# Carte-Marteaux.net
KiCad netlist of a schematic drawn in EAGLE
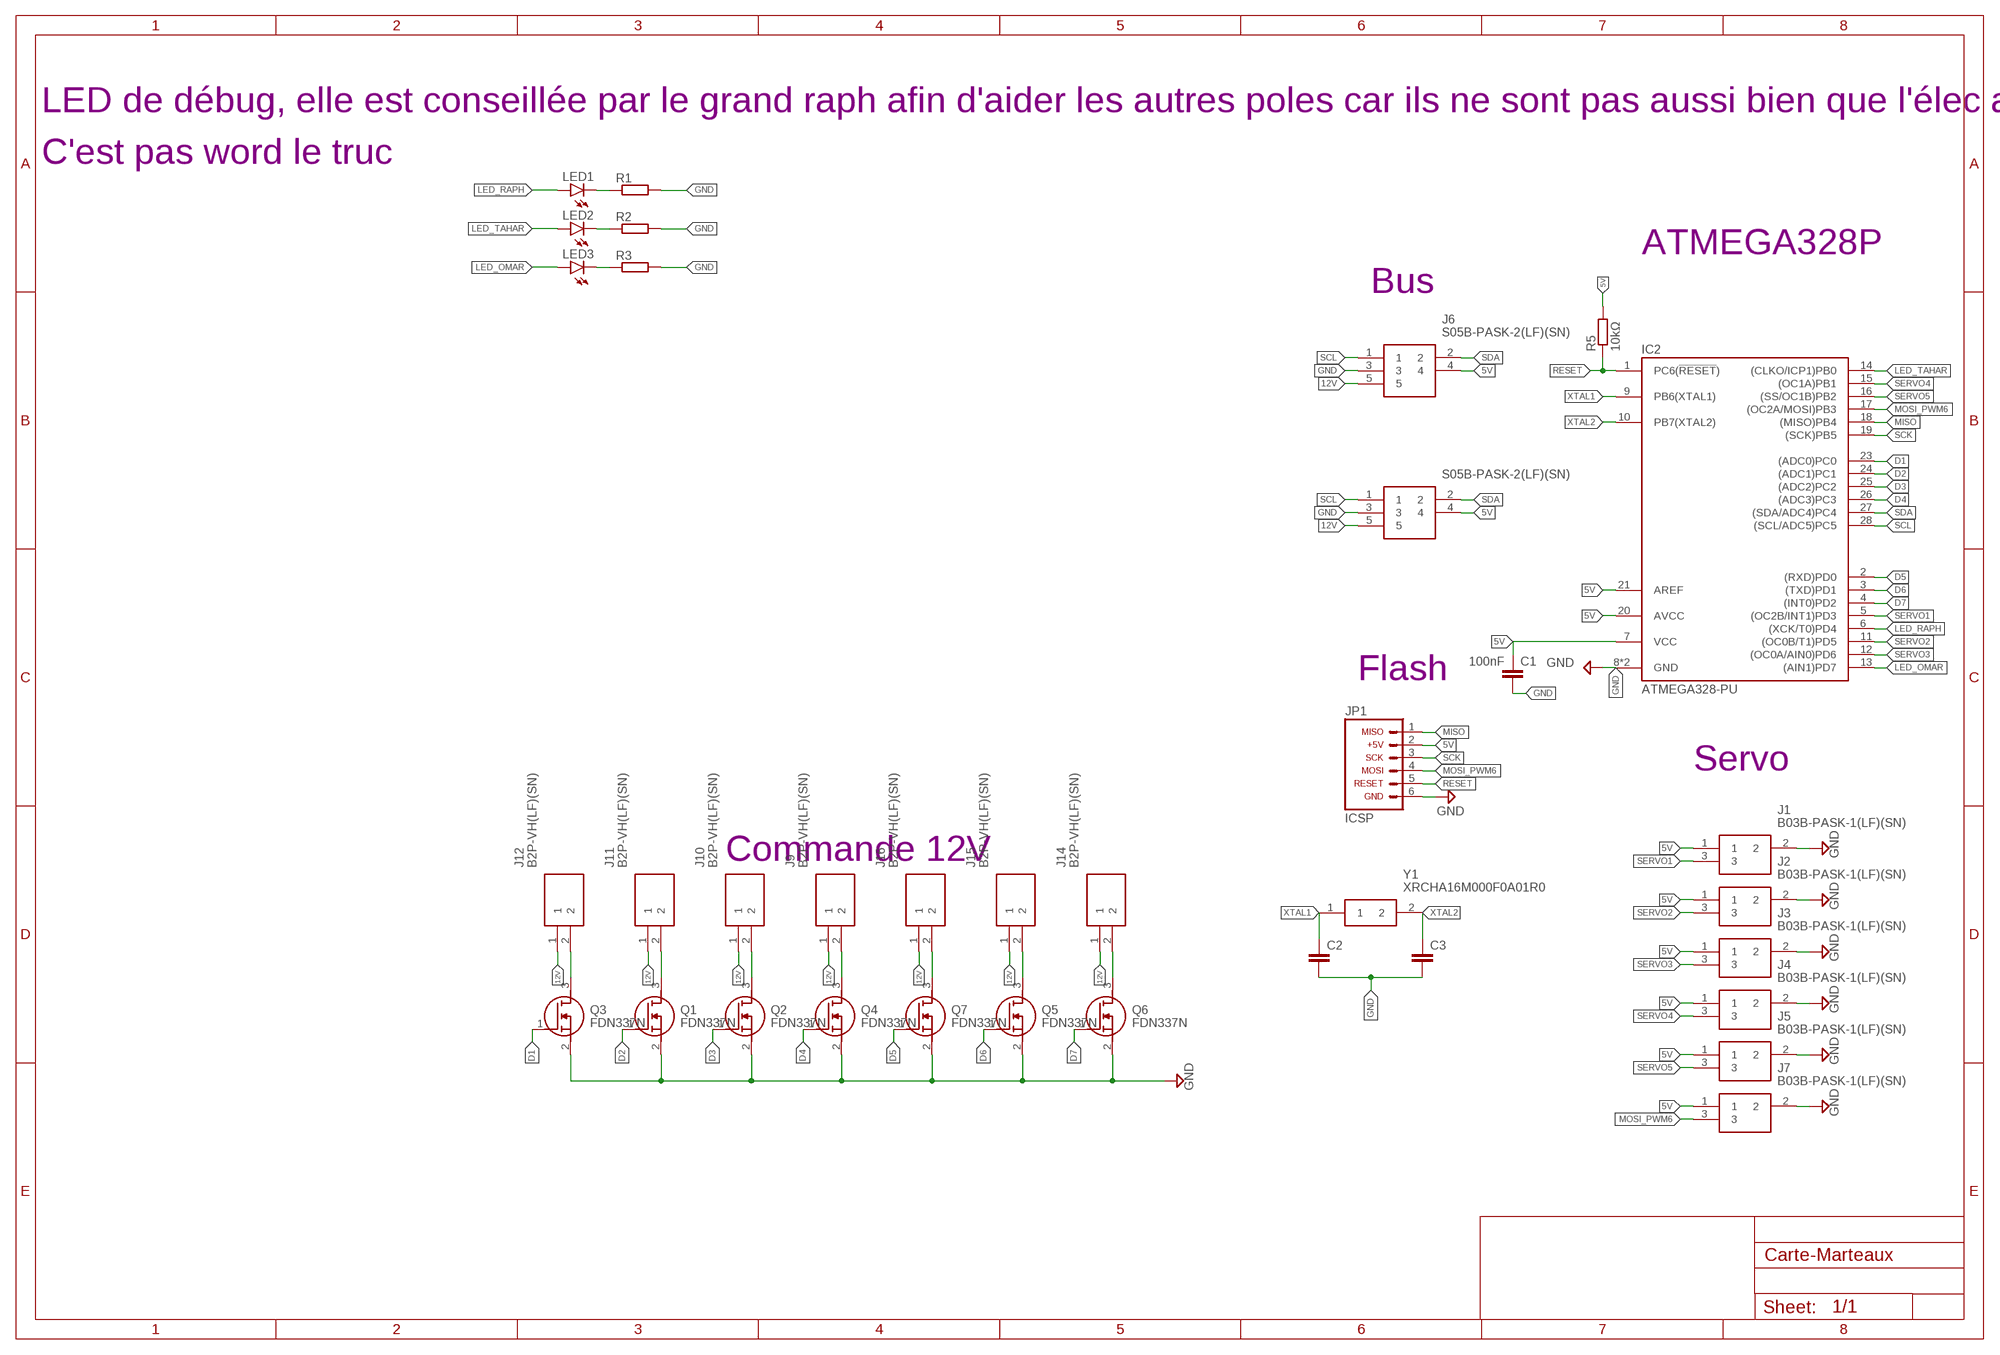
[diagram p0: schematic, sheet 1]

(export (version "E")
  (design (tool "Eeschema 10.0.6"))
  (components
    (comp (ref "C1")
      (value "100nF")
      (footprint "eagle-import:C0805")
      (libsource (lib "eagle-import") (part "C-EUC0805"))
    )
    (comp (ref "C2")
      (value "C-EUC0402")
      (footprint "eagle-import:C0402")
      (libsource (lib "eagle-import") (part "C-EUC0402"))
    )
    (comp (ref "C3")
      (value "C-EUC0402")
      (footprint "eagle-import:C0402")
      (libsource (lib "eagle-import") (part "C-EUC0402"))
    )
    (comp (ref "IC2")
      (value "ATMEGA328-PU")
      (footprint "eagle-import:DIL28")
      (fields (field (name "MF") "Microchip Technology"))
      (libsource (lib "eagle-import") (part "ATMEGA328-PU"))
    )
    (comp (ref "J1")
      (value "B03B-PASK-1(LF)(SN)")
      (footprint "eagle-import:B03BPASK1LFSN")
      (libsource (lib "eagle-import") (part "B03B-PASK-1(LF)(SN)"))
    )
    (comp (ref "J2")
      (value "B03B-PASK-1(LF)(SN)")
      (footprint "eagle-import:B03BPASK1LFSN")
      (libsource (lib "eagle-import") (part "B03B-PASK-1(LF)(SN)"))
    )
    (comp (ref "J3")
      (value "B03B-PASK-1(LF)(SN)")
      (footprint "eagle-import:B03BPASK1LFSN")
      (libsource (lib "eagle-import") (part "B03B-PASK-1(LF)(SN)"))
    )
    (comp (ref "J4")
      (value "B03B-PASK-1(LF)(SN)")
      (footprint "eagle-import:B03BPASK1LFSN")
      (libsource (lib "eagle-import") (part "B03B-PASK-1(LF)(SN)"))
    )
    (comp (ref "J5")
      (value "B03B-PASK-1(LF)(SN)")
      (footprint "eagle-import:B03BPASK1LFSN")
      (libsource (lib "eagle-import") (part "B03B-PASK-1(LF)(SN)"))
    )
    (comp (ref "J6")
      (value "S05B-PASK-2(LF)(SN)")
      (footprint "eagle-import:S05B-PASK-2(LF)(SN)")
      (libsource (lib "eagle-import") (part "S05B-PASK-2(LF)(SN)"))
    )
    (comp (ref "J7")
      (value "B03B-PASK-1(LF)(SN)")
      (footprint "eagle-import:B03BPASK1LFSN")
      (libsource (lib "eagle-import") (part "B03B-PASK-1(LF)(SN)"))
    )
    (comp (ref "J8")
      (value "S05B-PASK-2(LF)(SN)")
      (footprint "eagle-import:S05B-PASK-2(LF)(SN)")
      (libsource (lib "eagle-import") (part "S05B-PASK-2(LF)(SN)"))
    )
    (comp (ref "J9")
      (value "B2P-VH(LF)(SN)")
      (footprint "eagle-import:SHDR2W114P0X396_1X2_786X850X94")
      (fields (field (name "RS_PART_NUMBER") "8201147P"))
      (libsource (lib "eagle-import") (part "B2P-VH(LF)(SN)"))
    )
    (comp (ref "J10")
      (value "B2P-VH(LF)(SN)")
      (footprint "eagle-import:SHDR2W114P0X396_1X2_786X850X94")
      (fields (field (name "RS_PART_NUMBER") "8201147P"))
      (libsource (lib "eagle-import") (part "B2P-VH(LF)(SN)"))
    )
    (comp (ref "J11")
      (value "B2P-VH(LF)(SN)")
      (footprint "eagle-import:SHDR2W114P0X396_1X2_786X850X94")
      (fields (field (name "RS_PART_NUMBER") "8201147P"))
      (libsource (lib "eagle-import") (part "B2P-VH(LF)(SN)"))
    )
    (comp (ref "J12")
      (value "B2P-VH(LF)(SN)")
      (footprint "eagle-import:SHDR2W114P0X396_1X2_786X850X94")
      (fields (field (name "RS_PART_NUMBER") "8201147P"))
      (libsource (lib "eagle-import") (part "B2P-VH(LF)(SN)"))
    )
    (comp (ref "J14")
      (value "B2P-VH(LF)(SN)")
      (footprint "eagle-import:SHDR2W114P0X396_1X2_786X850X94")
      (fields (field (name "RS_PART_NUMBER") "8201147P"))
      (libsource (lib "eagle-import") (part "B2P-VH(LF)(SN)"))
    )
    (comp (ref "J15")
      (value "B2P-VH(LF)(SN)")
      (footprint "eagle-import:SHDR2W114P0X396_1X2_786X850X94")
      (fields (field (name "RS_PART_NUMBER") "8201147P"))
      (libsource (lib "eagle-import") (part "B2P-VH(LF)(SN)"))
    )
    (comp (ref "J16")
      (value "B2P-VH(LF)(SN)")
      (footprint "eagle-import:SHDR2W114P0X396_1X2_786X850X94")
      (fields (field (name "RS_PART_NUMBER") "8201147P"))
      (libsource (lib "eagle-import") (part "B2P-VH(LF)(SN)"))
    )
    (comp (ref "JP1")
      (value "ARDUINO_CONN-ICSP")
      (footprint "eagle-import:CONN-2X03")
      (libsource (lib "eagle-import") (part "ARDUINO_CONN-ICSP"))
    )
    (comp (ref "LED1")
      (value "LEDCHIP-LED0805")
      (footprint "eagle-import:CHIP-LED0805")
      (libsource (lib "eagle-import") (part "LEDCHIP-LED0805"))
    )
    (comp (ref "LED2")
      (value "LEDCHIP-LED0805")
      (footprint "eagle-import:CHIP-LED0805")
      (libsource (lib "eagle-import") (part "LEDCHIP-LED0805"))
    )
    (comp (ref "LED3")
      (value "LEDCHIP-LED0805")
      (footprint "eagle-import:CHIP-LED0805")
      (libsource (lib "eagle-import") (part "LEDCHIP-LED0805"))
    )
    (comp (ref "Q1")
      (value "FDN337N")
      (footprint "eagle-import:SOT95P237X112-3N")
      (fields (field (name "MOUSER_PART_NUMBER") "512-FDN337N") (field (name "RS_PART_NUMBER") "6710429P"))
      (libsource (lib "eagle-import") (part "FDN337N"))
    )
    (comp (ref "Q2")
      (value "FDN337N")
      (footprint "eagle-import:SOT95P237X112-3N")
      (fields (field (name "MOUSER_PART_NUMBER") "512-FDN337N") (field (name "RS_PART_NUMBER") "6710429P"))
      (libsource (lib "eagle-import") (part "FDN337N"))
    )
    (comp (ref "Q3")
      (value "FDN337N")
      (footprint "eagle-import:SOT95P237X112-3N")
      (fields (field (name "MOUSER_PART_NUMBER") "512-FDN337N") (field (name "RS_PART_NUMBER") "6710429P"))
      (libsource (lib "eagle-import") (part "FDN337N"))
    )
    (comp (ref "Q4")
      (value "FDN337N")
      (footprint "eagle-import:SOT95P237X112-3N")
      (fields (field (name "MOUSER_PART_NUMBER") "512-FDN337N") (field (name "RS_PART_NUMBER") "6710429P"))
      (libsource (lib "eagle-import") (part "FDN337N"))
    )
    (comp (ref "Q5")
      (value "FDN337N")
      (footprint "eagle-import:SOT95P237X112-3N")
      (fields (field (name "MOUSER_PART_NUMBER") "512-FDN337N") (field (name "RS_PART_NUMBER") "6710429P"))
      (libsource (lib "eagle-import") (part "FDN337N"))
    )
    (comp (ref "Q6")
      (value "FDN337N")
      (footprint "eagle-import:SOT95P237X112-3N")
      (fields (field (name "MOUSER_PART_NUMBER") "512-FDN337N") (field (name "RS_PART_NUMBER") "6710429P"))
      (libsource (lib "eagle-import") (part "FDN337N"))
    )
    (comp (ref "Q7")
      (value "FDN337N")
      (footprint "eagle-import:SOT95P237X112-3N")
      (fields (field (name "MOUSER_PART_NUMBER") "512-FDN337N") (field (name "RS_PART_NUMBER") "6710429P"))
      (libsource (lib "eagle-import") (part "FDN337N"))
    )
    (comp (ref "R1")
      (value "R-EU_R0805")
      (footprint "eagle-import:R0805")
      (libsource (lib "eagle-import") (part "R-EU_R0805"))
    )
    (comp (ref "R2")
      (value "R-EU_R0805")
      (footprint "eagle-import:R0805")
      (libsource (lib "eagle-import") (part "R-EU_R0805"))
    )
    (comp (ref "R3")
      (value "R-EU_R0805")
      (footprint "eagle-import:R0805")
      (libsource (lib "eagle-import") (part "R-EU_R0805"))
    )
    (comp (ref "R5")
      (value "10kΩ")
      (footprint "eagle-import:R0805")
      (libsource (lib "eagle-import") (part "R-EU_R0805"))
    )
    (comp (ref "Y1")
      (value "XRCHA16M000F0A01R0")
      (footprint "eagle-import:XRCHA")
      (fields
        (field (name "MOUSER_PART_NUMBER") "81-XRCHA16M000F0A1R0")
        (field (name "RS_PART_NUMBER") "1446622")
      )
      (libsource (lib "eagle-import") (part "XRCHA16M000F0A01R0"))
    )
  )
  (nets
    (net (code "1") (name "5V") (class "Default")
      (node (ref "C1") (pin "1") (pinfunction "1_1") (pintype "passive"))
      (node (ref "IC2") (pin "20") (pinfunction "AVCC_20") (pintype "power_in"))
      (node (ref "IC2") (pin "21") (pinfunction "AREF_21") (pintype "passive"))
      (node (ref "IC2") (pin "7") (pinfunction "VCC_7") (pintype "power_in"))
      (node (ref "J1") (pin "1") (pinfunction "1_1") (pintype "bidirectional"))
      (node (ref "J2") (pin "1") (pinfunction "1_1") (pintype "bidirectional"))
      (node (ref "J3") (pin "1") (pinfunction "1_1") (pintype "bidirectional"))
      (node (ref "J4") (pin "1") (pinfunction "1_1") (pintype "bidirectional"))
      (node (ref "J5") (pin "1") (pinfunction "1_1") (pintype "bidirectional"))
      (node (ref "J6") (pin "4") (pinfunction "4_4") (pintype "bidirectional"))
      (node (ref "J7") (pin "1") (pinfunction "1_1") (pintype "bidirectional"))
      (node (ref "J8") (pin "4") (pinfunction "4_4") (pintype "bidirectional"))
      (node (ref "JP1") (pin "2") (pinfunction "2_2") (pintype "passive"))
      (node (ref "R5") (pin "2") (pinfunction "2_2") (pintype "passive"))
    )
    (net (code "2") (name "12V") (class "Default")
      (node (ref "J10") (pin "1") (pinfunction "1_1") (pintype "bidirectional"))
      (node (ref "J11") (pin "1") (pinfunction "1_1") (pintype "bidirectional"))
      (node (ref "J12") (pin "1") (pinfunction "1_1") (pintype "bidirectional"))
      (node (ref "J14") (pin "1") (pinfunction "1_1") (pintype "bidirectional"))
      (node (ref "J15") (pin "1") (pinfunction "1_1") (pintype "bidirectional"))
      (node (ref "J16") (pin "1") (pinfunction "1_1") (pintype "bidirectional"))
      (node (ref "J6") (pin "5") (pinfunction "5_5") (pintype "bidirectional"))
      (node (ref "J8") (pin "5") (pinfunction "5_5") (pintype "bidirectional"))
      (node (ref "J9") (pin "1") (pinfunction "1_1") (pintype "bidirectional"))
    )
    (net (code "3") (name "D1") (class "Default")
      (node (ref "IC2") (pin "23") (pinfunction "(ADC0)PC0_23") (pintype "bidirectional"))
      (node (ref "Q3") (pin "1") (pinfunction "G_1") (pintype "bidirectional"))
    )
    (net (code "4") (name "D2") (class "Default")
      (node (ref "IC2") (pin "24") (pinfunction "(ADC1)PC1_24") (pintype "bidirectional"))
      (node (ref "Q1") (pin "1") (pinfunction "G_1") (pintype "bidirectional"))
    )
    (net (code "5") (name "D3") (class "Default")
      (node (ref "IC2") (pin "25") (pinfunction "(ADC2)PC2_25") (pintype "bidirectional"))
      (node (ref "Q2") (pin "1") (pinfunction "G_1") (pintype "bidirectional"))
    )
    (net (code "6") (name "D4") (class "Default")
      (node (ref "IC2") (pin "26") (pinfunction "(ADC3)PC3_26") (pintype "bidirectional"))
      (node (ref "Q4") (pin "1") (pinfunction "G_1") (pintype "bidirectional"))
    )
    (net (code "7") (name "D5") (class "Default")
      (node (ref "IC2") (pin "2") (pinfunction "(RXD)PD0_2") (pintype "bidirectional"))
      (node (ref "Q7") (pin "1") (pinfunction "G_1") (pintype "bidirectional"))
    )
    (net (code "8") (name "D6") (class "Default")
      (node (ref "IC2") (pin "3") (pinfunction "(TXD)PD1_3") (pintype "bidirectional"))
      (node (ref "Q5") (pin "1") (pinfunction "G_1") (pintype "bidirectional"))
    )
    (net (code "9") (name "D7") (class "Default")
      (node (ref "IC2") (pin "4") (pinfunction "(INT0)PD2_4") (pintype "bidirectional"))
      (node (ref "Q6") (pin "1") (pinfunction "G_1") (pintype "bidirectional"))
    )
    (net (code "10") (name "GND") (class "Default")
      (node (ref "C1") (pin "2") (pinfunction "2_2") (pintype "passive"))
      (node (ref "C2") (pin "2") (pinfunction "2_2") (pintype "passive"))
      (node (ref "C3") (pin "2") (pinfunction "2_2") (pintype "passive"))
      (node (ref "IC2") (pin "22") (pinfunction "GND_22") (pintype "power_in"))
      (node (ref "IC2") (pin "8") (pinfunction "GND_8") (pintype "power_in"))
      (node (ref "J1") (pin "2") (pinfunction "2_2") (pintype "bidirectional"))
      (node (ref "J2") (pin "2") (pinfunction "2_2") (pintype "bidirectional"))
      (node (ref "J3") (pin "2") (pinfunction "2_2") (pintype "bidirectional"))
      (node (ref "J4") (pin "2") (pinfunction "2_2") (pintype "bidirectional"))
      (node (ref "J5") (pin "2") (pinfunction "2_2") (pintype "bidirectional"))
      (node (ref "J6") (pin "3") (pinfunction "3_3") (pintype "bidirectional"))
      (node (ref "J7") (pin "2") (pinfunction "2_2") (pintype "bidirectional"))
      (node (ref "J8") (pin "3") (pinfunction "3_3") (pintype "bidirectional"))
      (node (ref "JP1") (pin "6") (pinfunction "6_6") (pintype "passive"))
      (node (ref "Q1") (pin "2") (pinfunction "S_2") (pintype "bidirectional"))
      (node (ref "Q2") (pin "2") (pinfunction "S_2") (pintype "bidirectional"))
      (node (ref "Q3") (pin "2") (pinfunction "S_2") (pintype "bidirectional"))
      (node (ref "Q4") (pin "2") (pinfunction "S_2") (pintype "bidirectional"))
      (node (ref "Q5") (pin "2") (pinfunction "S_2") (pintype "bidirectional"))
      (node (ref "Q6") (pin "2") (pinfunction "S_2") (pintype "bidirectional"))
      (node (ref "Q7") (pin "2") (pinfunction "S_2") (pintype "bidirectional"))
      (node (ref "R1") (pin "2") (pinfunction "2_2") (pintype "passive"))
      (node (ref "R2") (pin "2") (pinfunction "2_2") (pintype "passive"))
      (node (ref "R3") (pin "2") (pinfunction "2_2") (pintype "passive"))
    )
    (net (code "11") (name "LED_OMAR") (class "Default")
      (node (ref "IC2") (pin "13") (pinfunction "(AIN1)PD7_13") (pintype "bidirectional"))
      (node (ref "LED3") (pin "A") (pinfunction "A_A") (pintype "passive"))
    )
    (net (code "12") (name "LED_RAPH") (class "Default")
      (node (ref "IC2") (pin "6") (pinfunction "(XCK/T0)PD4_6") (pintype "bidirectional"))
      (node (ref "LED1") (pin "A") (pinfunction "A_A") (pintype "passive"))
    )
    (net (code "13") (name "LED_TAHAR") (class "Default")
      (node (ref "IC2") (pin "14") (pinfunction "(CLKO/ICP1)PB0_14") (pintype "bidirectional"))
      (node (ref "LED2") (pin "A") (pinfunction "A_A") (pintype "passive"))
    )
    (net (code "14") (name "MISO") (class "Default")
      (node (ref "IC2") (pin "18") (pinfunction "(MISO)PB4_18") (pintype "bidirectional"))
      (node (ref "JP1") (pin "1") (pinfunction "1_1") (pintype "passive"))
    )
    (net (code "15") (name "MOSI_PWM6") (class "Default")
      (node (ref "IC2") (pin "17") (pinfunction "(OC2A/MOSI)PB3_17") (pintype "bidirectional"))
      (node (ref "J7") (pin "3") (pinfunction "3_3") (pintype "bidirectional"))
      (node (ref "JP1") (pin "4") (pinfunction "4_4") (pintype "passive"))
    )
    (net (code "16") (name "Net-(LED1-PadC)") (class "Default")
      (node (ref "LED1") (pin "C") (pinfunction "C_C") (pintype "passive"))
      (node (ref "R1") (pin "1") (pinfunction "1_1") (pintype "passive"))
    )
    (net (code "17") (name "Net-(LED2-PadC)") (class "Default")
      (node (ref "LED2") (pin "C") (pinfunction "C_C") (pintype "passive"))
      (node (ref "R2") (pin "1") (pinfunction "1_1") (pintype "passive"))
    )
    (net (code "18") (name "Net-(LED3-PadC)") (class "Default")
      (node (ref "LED3") (pin "C") (pinfunction "C_C") (pintype "passive"))
      (node (ref "R3") (pin "1") (pinfunction "1_1") (pintype "passive"))
    )
    (net (code "19") (name "Net-(Q1-D)") (class "Default")
      (node (ref "J11") (pin "2") (pinfunction "2_2") (pintype "bidirectional"))
      (node (ref "Q1") (pin "3") (pinfunction "D_3") (pintype "bidirectional"))
    )
    (net (code "20") (name "Net-(Q2-D)") (class "Default")
      (node (ref "J10") (pin "2") (pinfunction "2_2") (pintype "bidirectional"))
      (node (ref "Q2") (pin "3") (pinfunction "D_3") (pintype "bidirectional"))
    )
    (net (code "21") (name "Net-(Q3-D)") (class "Default")
      (node (ref "J12") (pin "2") (pinfunction "2_2") (pintype "bidirectional"))
      (node (ref "Q3") (pin "3") (pinfunction "D_3") (pintype "bidirectional"))
    )
    (net (code "22") (name "Net-(Q4-D)") (class "Default")
      (node (ref "J9") (pin "2") (pinfunction "2_2") (pintype "bidirectional"))
      (node (ref "Q4") (pin "3") (pinfunction "D_3") (pintype "bidirectional"))
    )
    (net (code "23") (name "Net-(Q5-D)") (class "Default")
      (node (ref "J15") (pin "2") (pinfunction "2_2") (pintype "bidirectional"))
      (node (ref "Q5") (pin "3") (pinfunction "D_3") (pintype "bidirectional"))
    )
    (net (code "24") (name "Net-(Q6-D)") (class "Default")
      (node (ref "J14") (pin "2") (pinfunction "2_2") (pintype "bidirectional"))
      (node (ref "Q6") (pin "3") (pinfunction "D_3") (pintype "bidirectional"))
    )
    (net (code "25") (name "Net-(Q7-D)") (class "Default")
      (node (ref "J16") (pin "2") (pinfunction "2_2") (pintype "bidirectional"))
      (node (ref "Q7") (pin "3") (pinfunction "D_3") (pintype "bidirectional"))
    )
    (net (code "26") (name "RESET") (class "Default")
      (node (ref "IC2") (pin "1") (pinfunction "PC6(~{RESET})_1") (pintype "bidirectional"))
      (node (ref "JP1") (pin "5") (pinfunction "5_5") (pintype "passive"))
      (node (ref "R5") (pin "1") (pinfunction "1_1") (pintype "passive"))
    )
    (net (code "27") (name "SCK") (class "Default")
      (node (ref "IC2") (pin "19") (pinfunction "(SCK)PB5_19") (pintype "bidirectional"))
      (node (ref "JP1") (pin "3") (pinfunction "3_3") (pintype "passive"))
    )
    (net (code "28") (name "SCL") (class "Default")
      (node (ref "IC2") (pin "28") (pinfunction "(SCL/ADC5)PC5_28") (pintype "bidirectional"))
      (node (ref "J6") (pin "1") (pinfunction "1_1") (pintype "bidirectional"))
      (node (ref "J8") (pin "1") (pinfunction "1_1") (pintype "bidirectional"))
    )
    (net (code "29") (name "SDA") (class "Default")
      (node (ref "IC2") (pin "27") (pinfunction "(SDA/ADC4)PC4_27") (pintype "bidirectional"))
      (node (ref "J6") (pin "2") (pinfunction "2_2") (pintype "bidirectional"))
      (node (ref "J8") (pin "2") (pinfunction "2_2") (pintype "bidirectional"))
    )
    (net (code "30") (name "SERVO1") (class "Default")
      (node (ref "IC2") (pin "5") (pinfunction "(OC2B/INT1)PD3_5") (pintype "bidirectional"))
      (node (ref "J1") (pin "3") (pinfunction "3_3") (pintype "bidirectional"))
    )
    (net (code "31") (name "SERVO2") (class "Default")
      (node (ref "IC2") (pin "11") (pinfunction "(OC0B/T1)PD5_11") (pintype "bidirectional"))
      (node (ref "J2") (pin "3") (pinfunction "3_3") (pintype "bidirectional"))
    )
    (net (code "32") (name "SERVO3") (class "Default")
      (node (ref "IC2") (pin "12") (pinfunction "(OC0A/AIN0)PD6_12") (pintype "bidirectional"))
      (node (ref "J3") (pin "3") (pinfunction "3_3") (pintype "bidirectional"))
    )
    (net (code "33") (name "SERVO4") (class "Default")
      (node (ref "IC2") (pin "15") (pinfunction "(OC1A)PB1_15") (pintype "bidirectional"))
      (node (ref "J4") (pin "3") (pinfunction "3_3") (pintype "bidirectional"))
    )
    (net (code "34") (name "SERVO5") (class "Default")
      (node (ref "IC2") (pin "16") (pinfunction "(SS/OC1B)PB2_16") (pintype "bidirectional"))
      (node (ref "J5") (pin "3") (pinfunction "3_3") (pintype "bidirectional"))
    )
    (net (code "35") (name "XTAL1") (class "Default")
      (node (ref "C2") (pin "1") (pinfunction "1_1") (pintype "passive"))
      (node (ref "IC2") (pin "9") (pinfunction "PB6(XTAL1)_9") (pintype "bidirectional"))
      (node (ref "Y1") (pin "1") (pinfunction "1_1") (pintype "bidirectional"))
    )
    (net (code "36") (name "XTAL2") (class "Default")
      (node (ref "C3") (pin "1") (pinfunction "1_1") (pintype "passive"))
      (node (ref "IC2") (pin "10") (pinfunction "PB7(XTAL2)_10") (pintype "bidirectional"))
      (node (ref "Y1") (pin "2") (pinfunction "2_2") (pintype "bidirectional"))
    )
  )
)
